# Enclosure_100x68_BHWL3.net
KiCad netlist of a schematic drawn in EAGLE
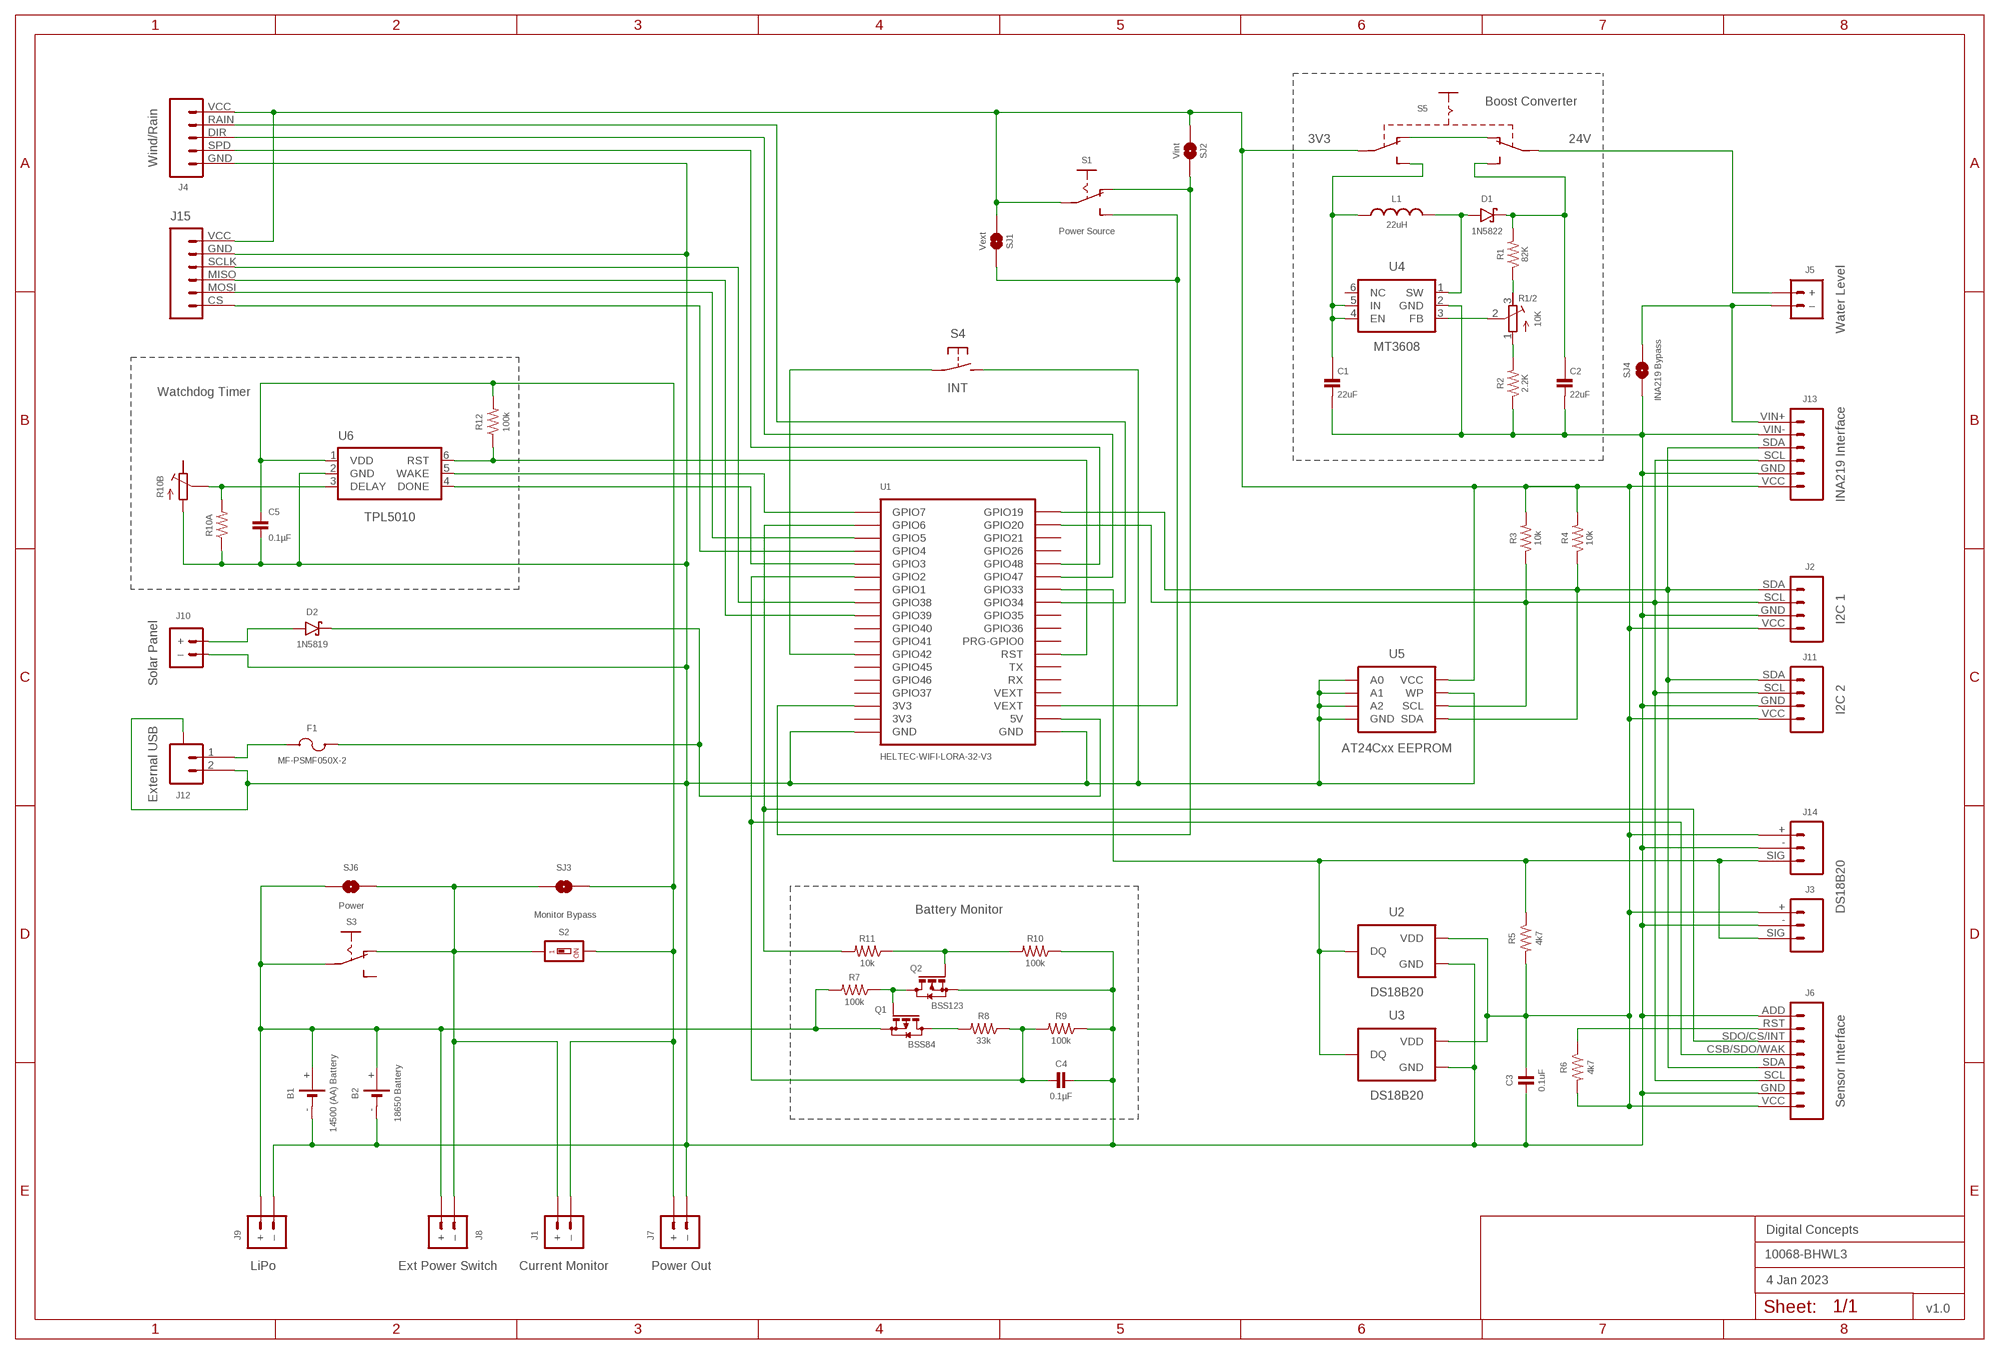
[diagram p0: schematic, sheet 1]

(export (version "E")
  (design (tool "Eeschema 10.0.6"))
  (components
    (comp (ref "B1")
      (value "14500 (AA) Battery")
      (footprint "eagle-import:BATTERY-14500")
      (libsource (lib "eagle-import") (part "BATTERY-HOLDER-14500(AA)"))
    )
    (comp (ref "B2")
      (value "18650 Battery")
      (footprint "eagle-import:BATTERY-18650")
      (libsource (lib "eagle-import") (part "BATTERY-HOLDER-18650"))
    )
    (comp (ref "C1")
      (value "22uF")
      (footprint "eagle-import:C1206")
      (libsource (lib "eagle-import") (part "CAPACITOR-1206"))
    )
    (comp (ref "C2")
      (value "22uF")
      (footprint "eagle-import:C1206")
      (libsource (lib "eagle-import") (part "CAPACITOR-1206"))
    )
    (comp (ref "C3")
      (value "0.1uF")
      (footprint "eagle-import:C0805")
      (libsource (lib "eagle-import") (part "CAPACITOR-0805"))
    )
    (comp (ref "C4")
      (value "0.1µF")
      (footprint "eagle-import:C0805")
      (libsource (lib "eagle-import") (part "CAPACITOR-0805"))
    )
    (comp (ref "C5")
      (value "0.1µF")
      (footprint "eagle-import:C0805")
      (libsource (lib "eagle-import") (part "CAPACITOR-0805"))
    )
    (comp (ref "D1")
      (value "1N5822")
      (footprint "eagle-import:DIODE_SMB")
      (libsource (lib "eagle-import") (part "DIODE-SCHOTTKY-1N5822"))
    )
    (comp (ref "D2")
      (value "1N5819")
      (footprint "eagle-import:SOD-123")
      (libsource (lib "eagle-import") (part "1N5819-SOD-123"))
    )
    (comp (ref "F1")
      (value "MF-PSMF050X-2")
      (footprint "eagle-import:F0805")
      (libsource (lib "eagle-import") (part "MF-PSMF050X-2"))
    )
    (comp (ref "J1")
      (value "Current Monitor")
      (footprint "eagle-import:JST-PH2.0-2-HORIZONTAL")
      (libsource (lib "eagle-import") (part "JST-PH2.0-2-HORIZONTALJST-PTH-2"))
    )
    (comp (ref "J2")
      (value "I2C 1")
      (footprint "eagle-import:JST-PH2.0-4-VERTICAL-I2C")
      (libsource (lib "eagle-import") (part "JST-PH2.0-4-VERTICAL-I2C"))
    )
    (comp (ref "J3")
      (value "DS18B20")
      (footprint "eagle-import:JST-PH2.0-3-VERTICAL-SIG")
      (libsource (lib "eagle-import") (part "JST-PH2.0-3-VERTICAL-DS18B20"))
    )
    (comp (ref "J4")
      (value "Wind/Rain")
      (footprint "eagle-import:JST-PH2.0-5-DUAL-WEATHER")
      (libsource (lib "eagle-import") (part "JST-PH2.0-5-DUAL-WEATHER"))
    )
    (comp (ref "J5")
      (value "Water Level")
      (footprint "eagle-import:JST-PH2.0-2-DUAL-POWER")
      (libsource (lib "eagle-import") (part "JST-PH2.0-2-DUAL-POWERJST-PTH-2"))
    )
    (comp (ref "J6")
      (value "Sensor Interface")
      (footprint "eagle-import:CONN_08-SENSOR")
      (libsource (lib "eagle-import") (part "HEADER-1X8-SENSOR"))
    )
    (comp (ref "J7")
      (value "Power Out")
      (footprint "eagle-import:JST-GH1.25-2-HORIZONTAL")
      (libsource (lib "eagle-import") (part "JST-GH1.25-2-HORIZONTAL-POWER"))
    )
    (comp (ref "J8")
      (value "Ext Power Switch")
      (footprint "eagle-import:JST-PH2.0-2-DUAL-POWER")
      (libsource (lib "eagle-import") (part "JST-PH2.0-2-DUAL-POWERJST-PTH-2"))
    )
    (comp (ref "J9")
      (value "LiPo")
      (footprint "eagle-import:JST-PH2.0-2-HORIZONTAL-POWER")
      (libsource (lib "eagle-import") (part "JST-PH2.0-2-HORIZONTAL-POWERJST-PTH-2"))
    )
    (comp (ref "J10")
      (value "Solar Panel")
      (footprint "eagle-import:JST-PH2.0-2-VERTICAL=POWER")
      (libsource (lib "eagle-import") (part "JST-PH2.0-2-VERTICAL"))
    )
    (comp (ref "J11")
      (value "I2C 2")
      (footprint "eagle-import:JST-PH2.0-4-HORIZONTAL")
      (libsource (lib "eagle-import") (part "JST-PH2.0-I2C-MALE-HORIZONTAL"))
    )
    (comp (ref "J12")
      (value "External USB")
      (footprint "eagle-import:JST-SH1.0-2-HORIZONTAL")
      (libsource (lib "eagle-import") (part "JST-SH1.0-2-SMD-HORIZONTAL"))
    )
    (comp (ref "J13")
      (value "INA219 Interface")
      (footprint "eagle-import:CONN_06-INA219")
      (libsource (lib "eagle-import") (part "INA219-I2C-MODULE"))
    )
    (comp (ref "J14")
      (value "JST-PH2.0-3-HORIZONTAL-DS18B20")
      (footprint "eagle-import:JST-PH2.0-DS18B20-HORIZONTAL")
      (libsource (lib "eagle-import") (part "JST-PH2.0-3-HORIZONTAL-DS18B20"))
    )
    (comp (ref "J15")
      (value "JST-PH2.0-6-HORIZONTAL-SPI")
      (footprint "eagle-import:JST-PH2.0-6-HORIZONTAL-SPI")
      (libsource (lib "eagle-import") (part "JST-PH2.0-6-HORIZONTAL-SPI"))
    )
    (comp (ref "L1")
      (value "22uH")
      (footprint "eagle-import:CDRH104R+6D28")
      (libsource (lib "eagle-import") (part "INDUCTOR-CDRH104R/6D28L5038P"))
    )
    (comp (ref "Q1")
      (value "BSS84")
      (footprint "eagle-import:SOT23-3")
      (libsource (lib "eagle-import") (part "BSS84"))
    )
    (comp (ref "Q2")
      (value "BSS123")
      (footprint "eagle-import:SOT23-3")
      (libsource (lib "eagle-import") (part "MOSFET-BSS123"))
    )
    (comp (ref "R1")
      (value "82K")
      (footprint "eagle-import:R0805")
      (libsource (lib "eagle-import") (part "RESISTORR0805"))
    )
    (comp (ref "R1/2")
      (value "10K")
      (footprint "eagle-import:RTRIM64P")
      (libsource (lib "eagle-import") (part "RESISTOR-TRIMM-BAOTER-HORIZONTAL"))
    )
    (comp (ref "R2")
      (value "2.2K")
      (footprint "eagle-import:R0805")
      (libsource (lib "eagle-import") (part "RESISTORR0805"))
    )
    (comp (ref "R3")
      (value "10k")
      (footprint "eagle-import:R0805")
      (libsource (lib "eagle-import") (part "RESISTORR0805"))
    )
    (comp (ref "R4")
      (value "10k")
      (footprint "eagle-import:R0805")
      (libsource (lib "eagle-import") (part "RESISTORR0805"))
    )
    (comp (ref "R5")
      (value "4k7")
      (footprint "eagle-import:R0805")
      (libsource (lib "eagle-import") (part "RESISTORR0805"))
    )
    (comp (ref "R6")
      (value "4k7")
      (footprint "eagle-import:R0805")
      (libsource (lib "eagle-import") (part "RESISTORR0805"))
    )
    (comp (ref "R7")
      (value "100k")
      (footprint "eagle-import:R0805")
      (libsource (lib "eagle-import") (part "RESISTORR0805"))
    )
    (comp (ref "R8")
      (value "33k")
      (footprint "eagle-import:R0805")
      (libsource (lib "eagle-import") (part "RESISTORR0805"))
    )
    (comp (ref "R9")
      (value "100k")
      (footprint "eagle-import:R0805")
      (libsource (lib "eagle-import") (part "RESISTORR0805"))
    )
    (comp (ref "R10")
      (value "100k")
      (footprint "eagle-import:R0805")
      (libsource (lib "eagle-import") (part "RESISTORR0805"))
    )
    (comp (ref "R10A")
      (value "RESISTORR0805")
      (footprint "eagle-import:R0805")
      (libsource (lib "eagle-import") (part "RESISTORR0805"))
    )
    (comp (ref "R10B")
      (value "RESISTOR-TRIMM-33")
      (footprint "eagle-import:RTRIM3_3")
      (libsource (lib "eagle-import") (part "RESISTOR-TRIMM-33"))
    )
    (comp (ref "R11")
      (value "10k")
      (footprint "eagle-import:R0805")
      (libsource (lib "eagle-import") (part "RESISTORR0805"))
    )
    (comp (ref "R12")
      (value "100k")
      (footprint "eagle-import:R0805")
      (libsource (lib "eagle-import") (part "RESISTORR0805"))
    )
    (comp (ref "S1")
      (value "Power Source")
      (footprint "eagle-import:SWITCH-SPDT-SMT")
      (libsource (lib "eagle-import") (part "SWITCH-SLIDE-SPDT-SMT"))
    )
    (comp (ref "S2")
      (value "Monitor Bypass")
      (footprint "eagle-import:SMD-001")
      (libsource (lib "eagle-import") (part "SWITCH-DIP-SWS001"))
    )
    (comp (ref "S3")
      (value "Power")
      (footprint "eagle-import:SWITCH-SPDT-PTH")
      (libsource (lib "eagle-import") (part "SWITCH-SLIDE-SPDT-PTH"))
    )
    (comp (ref "S4")
      (value "INT")
      (footprint "eagle-import:SWITCH-2-PAD")
      (libsource (lib "eagle-import") (part "SWITCH-MOMENTARY-2-PIN"))
    )
    (comp (ref "S5")
      (value "SWITCH-SLIDE-DPDT-PTH-S")
      (footprint "eagle-import:SWITCH-DPDT-PTH")
      (libsource (lib "eagle-import") (part "SWITCH-SLIDE-DPDT-PTH-S"))
    )
    (comp (ref "SJ1")
      (value "Vext")
      (footprint "eagle-import:SJ")
      (libsource (lib "eagle-import") (part "SJ"))
    )
    (comp (ref "SJ2")
      (value "Vint")
      (footprint "eagle-import:SJ-VIA-2")
      (libsource (lib "eagle-import") (part "SJ-V-2"))
    )
    (comp (ref "SJ3")
      (value "Monitor")
      (footprint "eagle-import:SJ")
      (libsource (lib "eagle-import") (part "SJ"))
    )
    (comp (ref "SJ4")
      (value "INA219 Bypass")
      (footprint "eagle-import:SJ")
      (libsource (lib "eagle-import") (part "SJ"))
    )
    (comp (ref "SJ6")
      (value "Power")
      (footprint "eagle-import:SJ")
      (libsource (lib "eagle-import") (part "SJ"))
    )
    (comp (ref "U1")
      (value "HELTEC-WIFI-LORA-32-V3")
      (footprint "eagle-import:HELTEC-WIFI-LORA-32-V3")
      (libsource (lib "eagle-import") (part "HELTEC-WIFI-LORA-32-V3"))
    )
    (comp (ref "U2")
      (value "DS18B20")
      (footprint "eagle-import:TO-92")
      (fields (field (name "MF") "Maxim Integrated"))
      (libsource (lib "eagle-import") (part "THERMOMETER-DS18B20"))
    )
    (comp (ref "U3")
      (value "DS18B20")
      (footprint "eagle-import:TO-92")
      (fields (field (name "MF") "Maxim Integrated"))
      (libsource (lib "eagle-import") (part "THERMOMETER-DS18B20"))
    )
    (comp (ref "U4")
      (value "MT3608")
      (footprint "eagle-import:SOT-23-6@1")
      (libsource (lib "eagle-import") (part "MT3608"))
    )
    (comp (ref "U5")
      (value "AT24Cxx EEPROM")
      (footprint "eagle-import:SOP-8")
      (libsource (lib "eagle-import") (part "AT24CXX-EEPROM"))
    )
    (comp (ref "U6")
      (value "TPL5010")
      (footprint "eagle-import:SOT-23-6")
      (libsource (lib "eagle-import") (part "TPL5010DDCR"))
    )
  )
  (nets
    (net (code "1") (name "Net-(D2-PadA)") (class "Default")
      (node (ref "D2") (pin "A") (pinfunction "A_A") (pintype "passive"))
      (node (ref "J10") (pin "+") (pinfunction "+_+") (pintype "power_in"))
    )
    (net (code "2") (name "Net-(D2-PadC)") (class "Default")
      (node (ref "D2") (pin "C") (pinfunction "C_C") (pintype "passive"))
      (node (ref "F1") (pin "1") (pinfunction "1_1") (pintype "passive"))
      (node (ref "U1") (pin "5V") (pinfunction "5V_5V") (pintype "bidirectional"))
    )
    (net (code "3") (name "Net-(F1-Pad2)") (class "Default")
      (node (ref "F1") (pin "2") (pinfunction "2_2") (pintype "passive"))
      (node (ref "J12") (pin "1") (pinfunction "1_1") (pintype "passive"))
    )
    (net (code "4") (name "Net-(J1-+)") (class "Default")
      (node (ref "J1") (pin "1") (pinfunction "+_1") (pintype "power_in"))
      (node (ref "J8") (pin "-") (pinfunction "–_-") (pintype "power_in"))
      (node (ref "S2") (pin "1") (pinfunction "1_1") (pintype "passive"))
      (node (ref "S3") (pin "1") (pinfunction "O_1") (pintype "passive"))
      (node (ref "SJ3") (pin "2") (pinfunction "2_2") (pintype "passive"))
      (node (ref "SJ6") (pin "1") (pinfunction "1_1") (pintype "passive"))
    )
    (net (code "5") (name "Net-(J1-–)") (class "Default")
      (node (ref "C5") (pin "1") (pinfunction "1_1") (pintype "passive"))
      (node (ref "J1") (pin "2") (pinfunction "–_2") (pintype "power_in"))
      (node (ref "J7") (pin "+") (pinfunction "+_+") (pintype "power_in"))
      (node (ref "R12") (pin "2") (pinfunction "2_2") (pintype "passive"))
      (node (ref "S2") (pin "2") (pinfunction "2_2") (pintype "passive"))
      (node (ref "SJ3") (pin "1") (pinfunction "1_1") (pintype "passive"))
      (node (ref "U6") (pin "1") (pinfunction "VDD_1") (pintype "power_in"))
    )
    (net (code "6") (name "Net-(J4-2)") (class "Default")
      (node (ref "J4") (pin "RAIN") (pinfunction "2_RAIN") (pintype "passive"))
      (node (ref "U1") (pin "GPIO34") (pinfunction "GPIO34_GPIO34") (pintype "bidirectional"))
    )
    (net (code "7") (name "Net-(J4-3)") (class "Default")
      (node (ref "J4") (pin "DIR") (pinfunction "3_DIR") (pintype "passive"))
      (node (ref "U1") (pin "GPIO47") (pinfunction "GPIO47_GPIO47") (pintype "bidirectional"))
    )
    (net (code "8") (name "Net-(J4-4)") (class "Default")
      (node (ref "J4") (pin "SPD") (pinfunction "4_SPD") (pintype "passive"))
      (node (ref "U1") (pin "GPIO48") (pinfunction "GPIO48_GPIO48") (pintype "bidirectional"))
    )
    (net (code "9") (name "Net-(J6-5)") (class "Default")
      (node (ref "C4") (pin "1") (pinfunction "1_1") (pintype "passive"))
      (node (ref "J6") (pin "CSB/SDO/WAK") (pinfunction "5_CSB/SDO/WAK") (pintype "passive"))
      (node (ref "R8") (pin "1") (pinfunction "1_1") (pintype "passive"))
      (node (ref "R9") (pin "2") (pinfunction "2_2") (pintype "passive"))
      (node (ref "U1") (pin "GPIO2") (pinfunction "GPIO2_GPIO2") (pintype "bidirectional"))
    )
    (net (code "10") (name "Net-(J6-6)") (class "Default")
      (node (ref "J6") (pin "SDO/CS/INT") (pinfunction "6_SDO/CS/INT") (pintype "passive"))
      (node (ref "R11") (pin "2") (pinfunction "2_2") (pintype "passive"))
      (node (ref "U1") (pin "GPIO6") (pinfunction "GPIO6_GPIO6") (pintype "bidirectional"))
    )
    (net (code "11") (name "Net-(J6-7)") (class "Default")
      (node (ref "J6") (pin "RST") (pinfunction "7_RST") (pintype "passive"))
      (node (ref "R6") (pin "1") (pinfunction "1_1") (pintype "passive"))
    )
    (net (code "12") (name "Net-(J10-–)") (class "Default")
      (node (ref "B1") (pin "-") (pinfunction "-_-") (pintype "power_in"))
      (node (ref "B2") (pin "-") (pinfunction "-_-") (pintype "power_in"))
      (node (ref "C1") (pin "2") (pinfunction "2_2") (pintype "passive"))
      (node (ref "C2") (pin "2") (pinfunction "2_2") (pintype "passive"))
      (node (ref "C3") (pin "2") (pinfunction "2_2") (pintype "passive"))
      (node (ref "C4") (pin "2") (pinfunction "2_2") (pintype "passive"))
      (node (ref "C5") (pin "2") (pinfunction "2_2") (pintype "passive"))
      (node (ref "J10") (pin "-") (pinfunction "–_-") (pintype "power_in"))
      (node (ref "J11") (pin "GND") (pinfunction "2_GND") (pintype "passive"))
      (node (ref "J12") (pin "2") (pinfunction "2_2") (pintype "passive"))
      (node (ref "J12") (pin "A@1") (pinfunction "A_A@1") (pintype "power_in"))
      (node (ref "J12") (pin "A@2") (pinfunction "A_A@2") (pintype "power_in"))
      (node (ref "J13") (pin "GND") (pinfunction "2_GND") (pintype "passive"))
      (node (ref "J13") (pin "VIN-") (pinfunction "5_VIN-") (pintype "passive"))
      (node (ref "J14") (pin "-") (pinfunction "2_-") (pintype "passive"))
      (node (ref "J15") (pin "GND") (pinfunction "5_GND") (pintype "passive"))
      (node (ref "J2") (pin "GND") (pinfunction "3_GND") (pintype "passive"))
      (node (ref "J3") (pin "-") (pinfunction "2_-") (pintype "passive"))
      (node (ref "J4") (pin "GND") (pinfunction "5_GND") (pintype "passive"))
      (node (ref "J6") (pin "ADD") (pinfunction "8_ADD") (pintype "passive"))
      (node (ref "J6") (pin "GND") (pinfunction "2_GND") (pintype "passive"))
      (node (ref "J7") (pin "-") (pinfunction "–_-") (pintype "power_in"))
      (node (ref "J9") (pin "-") (pinfunction "–_-") (pintype "power_in"))
      (node (ref "Q2") (pin "2") (pinfunction "S_2") (pintype "passive"))
      (node (ref "R10") (pin "1") (pinfunction "1_1") (pintype "passive"))
      (node (ref "R10A") (pin "1") (pinfunction "1_1") (pintype "passive"))
      (node (ref "R10B") (pin "1") (pinfunction "A_1") (pintype "passive"))
      (node (ref "R2") (pin "1") (pinfunction "1_1") (pintype "passive"))
      (node (ref "R9") (pin "1") (pinfunction "1_1") (pintype "passive"))
      (node (ref "S4") (pin "P$2") (pinfunction "S_P$2") (pintype "passive"))
      (node (ref "SJ4") (pin "1") (pinfunction "1_1") (pintype "passive"))
      (node (ref "U1") (pin "GND@1") (pinfunction "GND_GND@1") (pintype "bidirectional"))
      (node (ref "U1") (pin "GND@36") (pinfunction "GND_GND@36") (pintype "bidirectional"))
      (node (ref "U2") (pin "1") (pinfunction "GND_1") (pintype "power_in"))
      (node (ref "U3") (pin "1") (pinfunction "GND_1") (pintype "power_in"))
      (node (ref "U4") (pin "2") (pinfunction "GND_2") (pintype "power_in"))
      (node (ref "U5") (pin "P$1") (pinfunction "A0_P$1") (pintype "bidirectional"))
      (node (ref "U5") (pin "P$2") (pinfunction "A1_P$2") (pintype "bidirectional"))
      (node (ref "U5") (pin "P$3") (pinfunction "A2_P$3") (pintype "bidirectional"))
      (node (ref "U5") (pin "P$4") (pinfunction "GND_P$4") (pintype "bidirectional"))
      (node (ref "U5") (pin "P$7") (pinfunction "WP_P$7") (pintype "bidirectional"))
      (node (ref "U6") (pin "2") (pinfunction "GND_2") (pintype "power_in"))
    )
    (net (code "13") (name "Net-(J11-1)") (class "Default")
      (node (ref "C3") (pin "1") (pinfunction "1_1") (pintype "passive"))
      (node (ref "J11") (pin "VCC") (pinfunction "1_VCC") (pintype "passive"))
      (node (ref "J13") (pin "VCC") (pinfunction "1_VCC") (pintype "passive"))
      (node (ref "J14") (pin "+") (pinfunction "3_+") (pintype "passive"))
      (node (ref "J15") (pin "VCC") (pinfunction "6_VCC") (pintype "passive"))
      (node (ref "J2") (pin "VCC") (pinfunction "4_VCC") (pintype "passive"))
      (node (ref "J3") (pin "+") (pinfunction "3_+") (pintype "passive"))
      (node (ref "J4") (pin "VCC") (pinfunction "1_VCC") (pintype "passive"))
      (node (ref "J6") (pin "VCC") (pinfunction "1_VCC") (pintype "passive"))
      (node (ref "R3") (pin "2") (pinfunction "2_2") (pintype "passive"))
      (node (ref "R4") (pin "2") (pinfunction "2_2") (pintype "passive"))
      (node (ref "R5") (pin "2") (pinfunction "2_2") (pintype "passive"))
      (node (ref "R6") (pin "2") (pinfunction "2_2") (pintype "passive"))
      (node (ref "S1") (pin "2") (pinfunction "P_2") (pintype "passive"))
      (node (ref "S5") (pin "P$5") (pinfunction "P2_P$5") (pintype "passive"))
      (node (ref "SJ1") (pin "2") (pinfunction "2_2") (pintype "passive"))
      (node (ref "SJ2") (pin "2") (pinfunction "2_2") (pintype "passive"))
      (node (ref "SJ2") (pin "2@V") (pinfunction "2_2@V") (pintype "passive"))
      (node (ref "U2") (pin "3") (pinfunction "VDD_3") (pintype "power_in"))
      (node (ref "U3") (pin "3") (pinfunction "VDD_3") (pintype "power_in"))
      (node (ref "U5") (pin "P$8") (pinfunction "VCC_P$8") (pintype "bidirectional"))
    )
    (net (code "14") (name "Net-(J11-3)") (class "Default")
      (node (ref "J11") (pin "SCL") (pinfunction "3_SCL") (pintype "passive"))
      (node (ref "J13") (pin "SCL") (pinfunction "3_SCL") (pintype "passive"))
      (node (ref "J2") (pin "SCL") (pinfunction "2_SCL") (pintype "passive"))
      (node (ref "J6") (pin "SCL") (pinfunction "3_SCL") (pintype "passive"))
      (node (ref "R3") (pin "1") (pinfunction "1_1") (pintype "passive"))
      (node (ref "U1") (pin "GPIO20") (pinfunction "GPIO20_GPIO20") (pintype "bidirectional"))
      (node (ref "U5") (pin "P$6") (pinfunction "SCL_P$6") (pintype "bidirectional"))
    )
    (net (code "15") (name "Net-(J11-4)") (class "Default")
      (node (ref "J11") (pin "SDA") (pinfunction "4_SDA") (pintype "passive"))
      (node (ref "J13") (pin "SDA") (pinfunction "4_SDA") (pintype "passive"))
      (node (ref "J2") (pin "SDA") (pinfunction "1_SDA") (pintype "passive"))
      (node (ref "J6") (pin "SDA") (pinfunction "4_SDA") (pintype "passive"))
      (node (ref "R4") (pin "1") (pinfunction "1_1") (pintype "passive"))
      (node (ref "U1") (pin "GPIO19") (pinfunction "GPIO19_GPIO19") (pintype "bidirectional"))
      (node (ref "U5") (pin "P$5") (pinfunction "SDA_P$5") (pintype "bidirectional"))
    )
    (net (code "16") (name "Net-(J13-6)") (class "Default")
      (node (ref "J13") (pin "VIN+") (pinfunction "6_VIN+") (pintype "passive"))
      (node (ref "J5") (pin "-") (pinfunction "–_-") (pintype "power_in"))
      (node (ref "SJ4") (pin "2") (pinfunction "2_2") (pintype "passive"))
    )
    (net (code "17") (name "Net-(J14-1)") (class "Default")
      (node (ref "J14") (pin "SIG") (pinfunction "1_SIG") (pintype "passive"))
      (node (ref "J3") (pin "SIG") (pinfunction "1_SIG") (pintype "passive"))
      (node (ref "R5") (pin "1") (pinfunction "1_1") (pintype "passive"))
      (node (ref "U1") (pin "GPIO33") (pinfunction "GPIO33_GPIO33") (pintype "bidirectional"))
      (node (ref "U2") (pin "2") (pinfunction "DQ_2") (pintype "bidirectional"))
      (node (ref "U3") (pin "2") (pinfunction "DQ_2") (pintype "bidirectional"))
    )
    (net (code "18") (name "Net-(J15-1)") (class "Default")
      (node (ref "J15") (pin "CS") (pinfunction "1_CS") (pintype "passive"))
      (node (ref "U1") (pin "GPIO4") (pinfunction "GPIO4_GPIO4") (pintype "bidirectional"))
    )
    (net (code "19") (name "Net-(J15-2)") (class "Default")
      (node (ref "J15") (pin "MOSI") (pinfunction "2_MOSI") (pintype "passive"))
      (node (ref "U1") (pin "GPIO5") (pinfunction "GPIO5_GPIO5") (pintype "bidirectional"))
    )
    (net (code "20") (name "Net-(J15-3)") (class "Default")
      (node (ref "J15") (pin "MISO") (pinfunction "3_MISO") (pintype "passive"))
      (node (ref "U1") (pin "GPIO39") (pinfunction "GPIO39_GPIO39") (pintype "bidirectional"))
    )
    (net (code "21") (name "Net-(J15-4)") (class "Default")
      (node (ref "J15") (pin "SCLK") (pinfunction "4_SCLK") (pintype "passive"))
      (node (ref "U1") (pin "GPIO38") (pinfunction "GPIO38_GPIO38") (pintype "bidirectional"))
    )
    (net (code "22") (name "Net-(Q1-D)") (class "Default")
      (node (ref "Q1") (pin "3") (pinfunction "D_3") (pintype "passive"))
      (node (ref "R8") (pin "2") (pinfunction "2_2") (pintype "passive"))
    )
    (net (code "23") (name "Net-(Q1-G)") (class "Default")
      (node (ref "Q1") (pin "1") (pinfunction "G_1") (pintype "passive"))
      (node (ref "Q2") (pin "3") (pinfunction "D_3") (pintype "passive"))
      (node (ref "R7") (pin "1") (pinfunction "1_1") (pintype "passive"))
    )
    (net (code "24") (name "Net-(Q1-S)") (class "Default")
      (node (ref "B1") (pin "+") (pinfunction "+_+") (pintype "power_in"))
      (node (ref "B2") (pin "+") (pinfunction "+_+") (pintype "power_in"))
      (node (ref "J8") (pin "+") (pinfunction "+_+") (pintype "power_in"))
      (node (ref "J9") (pin "+") (pinfunction "+_+") (pintype "power_in"))
      (node (ref "Q1") (pin "2") (pinfunction "S_2") (pintype "passive"))
      (node (ref "R7") (pin "2") (pinfunction "2_2") (pintype "passive"))
      (node (ref "S3") (pin "2") (pinfunction "P_2") (pintype "passive"))
      (node (ref "SJ6") (pin "2") (pinfunction "2_2") (pintype "passive"))
    )
    (net (code "25") (name "Net-(Q2-G)") (class "Default")
      (node (ref "Q2") (pin "1") (pinfunction "G_1") (pintype "passive"))
      (node (ref "R10") (pin "2") (pinfunction "2_2") (pintype "passive"))
      (node (ref "R11") (pin "1") (pinfunction "1_1") (pintype "passive"))
    )
    (net (code "26") (name "Net-(R1/2-A)") (class "Default")
      (node (ref "R1/2") (pin "1") (pinfunction "A_1") (pintype "passive"))
      (node (ref "R2") (pin "2") (pinfunction "2_2") (pintype "passive"))
    )
    (net (code "27") (name "Net-(R1/2-E)") (class "Default")
      (node (ref "R1") (pin "1") (pinfunction "1_1") (pintype "passive"))
      (node (ref "R1/2") (pin "3") (pinfunction "E_3") (pintype "passive"))
    )
    (net (code "28") (name "Net-(R1/2-S)") (class "Default")
      (node (ref "R1/2") (pin "2") (pinfunction "S_2") (pintype "passive"))
      (node (ref "U4") (pin "3") (pinfunction "FB_3") (pintype "input"))
    )
    (net (code "29") (name "Net-(R10B-S)") (class "Default")
      (node (ref "R10A") (pin "2") (pinfunction "2_2") (pintype "passive"))
      (node (ref "R10B") (pin "2") (pinfunction "S_2") (pintype "passive"))
      (node (ref "U6") (pin "3") (pinfunction "DELAY_3") (pintype "input"))
    )
    (net (code "30") (name "Net-(S1-O)") (class "Default")
      (node (ref "S1") (pin "1") (pinfunction "O_1") (pintype "passive"))
      (node (ref "SJ2") (pin "1") (pinfunction "1_1") (pintype "passive"))
      (node (ref "U1") (pin "3V3@34") (pinfunction "3V3_3V3@34") (pintype "bidirectional"))
    )
    (net (code "31") (name "Net-(S1-S)") (class "Default")
      (node (ref "S1") (pin "3") (pinfunction "S_3") (pintype "passive"))
      (node (ref "SJ1") (pin "1") (pinfunction "1_1") (pintype "passive"))
      (node (ref "U1") (pin "VEXT@3") (pinfunction "VEXT_VEXT@3") (pintype "bidirectional"))
    )
    (net (code "32") (name "Net-(S4-P)") (class "Default")
      (node (ref "S4") (pin "P$1") (pinfunction "P_P$1") (pintype "passive"))
      (node (ref "U1") (pin "GPIO42") (pinfunction "GPIO42_GPIO42") (pintype "bidirectional"))
    )
    (net (code "33") (name "Net-(S5-O1)") (class "Default")
      (node (ref "S5") (pin "P$1") (pinfunction "O1_P$1") (pintype "passive"))
      (node (ref "S5") (pin "P$4") (pinfunction "O2_P$4") (pintype "passive"))
    )
    (net (code "34") (name "Net-(S5-P1)") (class "Default")
      (node (ref "J5") (pin "+") (pinfunction "+_+") (pintype "power_in"))
      (node (ref "S5") (pin "P$2") (pinfunction "P1_P$2") (pintype "passive"))
    )
    (net (code "35") (name "Net-(S5-S1)") (class "Default")
      (node (ref "C2") (pin "1") (pinfunction "1_1") (pintype "passive"))
      (node (ref "D1") (pin "C") (pinfunction "C_C") (pintype "passive"))
      (node (ref "R1") (pin "2") (pinfunction "2_2") (pintype "passive"))
      (node (ref "S5") (pin "P$3") (pinfunction "S1_P$3") (pintype "passive"))
    )
    (net (code "36") (name "Net-(S5-S2)") (class "Default")
      (node (ref "C1") (pin "1") (pinfunction "1_1") (pintype "passive"))
      (node (ref "L1") (pin "2") (pinfunction "2_2") (pintype "passive"))
      (node (ref "S5") (pin "P$6") (pinfunction "S2_P$6") (pintype "passive"))
      (node (ref "U4") (pin "4") (pinfunction "EN_4") (pintype "input"))
      (node (ref "U4") (pin "5") (pinfunction "IN_5") (pintype "power_in"))
    )
    (net (code "37") (name "Net-(U4-SW)") (class "Default")
      (node (ref "D1") (pin "A") (pinfunction "A_A") (pintype "passive"))
      (node (ref "L1") (pin "1") (pinfunction "1_1") (pintype "passive"))
      (node (ref "U4") (pin "1") (pinfunction "SW_1") (pintype "power_in"))
    )
    (net (code "38") (name "Net-(U6-DONE)") (class "Default")
      (node (ref "U1") (pin "GPIO3") (pinfunction "GPIO3_GPIO3") (pintype "bidirectional"))
      (node (ref "U6") (pin "4") (pinfunction "DONE_4") (pintype "input"))
    )
    (net (code "39") (name "Net-(U6-RST)") (class "Default")
      (node (ref "R12") (pin "1") (pinfunction "1_1") (pintype "passive"))
      (node (ref "U1") (pin "RST") (pinfunction "RST_RST") (pintype "bidirectional"))
      (node (ref "U6") (pin "6") (pinfunction "RST_6") (pintype "output"))
    )
    (net (code "40") (name "Net-(U6-WAKE)") (class "Default")
      (node (ref "U1") (pin "GPIO7") (pinfunction "GPIO7_GPIO7") (pintype "bidirectional"))
      (node (ref "U6") (pin "5") (pinfunction "WAKE_5") (pintype "output"))
    )
    (net (code "41") (name "unconnected-(R10B-E-Pad3)") (class "Default")
      (node (ref "R10B") (pin "3") (pinfunction "E_3") (pintype "passive"))
    )
    (net (code "42") (name "unconnected-(S3-S-Pad3)") (class "Default")
      (node (ref "S3") (pin "3") (pinfunction "S_3") (pintype "passive"))
    )
    (net (code "43") (name "unconnected-(U1-3V3-Pad3V3@35)") (class "Default")
      (node (ref "U1") (pin "3V3@35") (pinfunction "3V3_3V3@35") (pintype "bidirectional"))
    )
    (net (code "44") (name "unconnected-(U1-PRG-GPIO0-PadGPIO0)") (class "Default")
      (node (ref "U1") (pin "GPIO0") (pinfunction "PRG-GPIO0_GPIO0") (pintype "bidirectional"))
    )
    (net (code "45") (name "unconnected-(U1-PadGPIO1)") (class "Default")
      (node (ref "U1") (pin "GPIO1") (pinfunction "GPIO1_GPIO1") (pintype "bidirectional"))
    )
    (net (code "46") (name "unconnected-(U1-PadGPIO21)") (class "Default")
      (node (ref "U1") (pin "GPIO21") (pinfunction "GPIO21_GPIO21") (pintype "bidirectional"))
    )
    (net (code "47") (name "unconnected-(U1-PadGPIO26)") (class "Default")
      (node (ref "U1") (pin "GPIO26") (pinfunction "GPIO26_GPIO26") (pintype "bidirectional"))
    )
    (net (code "48") (name "unconnected-(U1-PadGPIO35)") (class "Default")
      (node (ref "U1") (pin "GPIO35") (pinfunction "GPIO35_GPIO35") (pintype "bidirectional"))
    )
    (net (code "49") (name "unconnected-(U1-PadGPIO36)") (class "Default")
      (node (ref "U1") (pin "GPIO36") (pinfunction "GPIO36_GPIO36") (pintype "bidirectional"))
    )
    (net (code "50") (name "unconnected-(U1-PadGPIO37)") (class "Default")
      (node (ref "U1") (pin "GPIO37") (pinfunction "GPIO37_GPIO37") (pintype "bidirectional"))
    )
    (net (code "51") (name "unconnected-(U1-PadGPIO40)") (class "Default")
      (node (ref "U1") (pin "GPIO40") (pinfunction "GPIO40_GPIO40") (pintype "bidirectional"))
    )
    (net (code "52") (name "unconnected-(U1-PadGPIO41)") (class "Default")
      (node (ref "U1") (pin "GPIO41") (pinfunction "GPIO41_GPIO41") (pintype "bidirectional"))
    )
    (net (code "53") (name "unconnected-(U1-PadGPIO45)") (class "Default")
      (node (ref "U1") (pin "GPIO45") (pinfunction "GPIO45_GPIO45") (pintype "bidirectional"))
    )
    (net (code "54") (name "unconnected-(U1-PadGPIO46)") (class "Default")
      (node (ref "U1") (pin "GPIO46") (pinfunction "GPIO46_GPIO46") (pintype "bidirectional"))
    )
    (net (code "55") (name "unconnected-(U1-PadRX)") (class "Default")
      (node (ref "U1") (pin "RX") (pinfunction "RX_RX") (pintype "bidirectional"))
    )
    (net (code "56") (name "unconnected-(U1-PadTX)") (class "Default")
      (node (ref "U1") (pin "TX") (pinfunction "TX_TX") (pintype "bidirectional"))
    )
    (net (code "57") (name "unconnected-(U1-VEXT-PadVEXT@4)") (class "Default")
      (node (ref "U1") (pin "VEXT@4") (pinfunction "VEXT_VEXT@4") (pintype "bidirectional"))
    )
    (net (code "58") (name "unconnected-(U4-NC-Pad6)") (class "Default")
      (node (ref "U4") (pin "6") (pinfunction "NC_6") (pintype "no_connect"))
    )
  )
)
